# PSU.net
KiCad netlist of a schematic drawn in Altium Designer
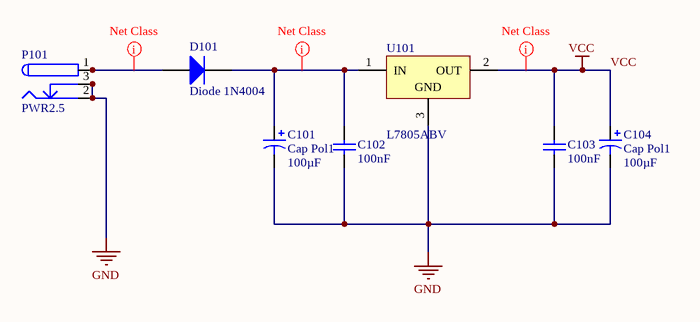
[diagram p0: PSU.SchDoc]

(export (version "E")
  (design (tool "Eeschema 10.0.6"))
  (components
    (comp (ref "C101")
      (value "Cap Pol1")
      (footprint "Tantalum_D")
      (description "Polarized Capacitor (Radial)")
      (fields (field (name "ALTIUM_VALUE") "100µF") (field (name "PUBLISHER") "Altium Limited"))
      (libsource (lib "Miscellaneous Devices") (part "Cap Pol1"))
    )
    (comp (ref "C102")
      (value "100nF")
      (footprint "RCL 0805")
      (description "Capacitor (Semiconductor SIM Model)")
      (fields (field (name "Comment") "Cap Semi") (field (name "PUBLISHER") "Altium Limited"))
      (libsource (lib "Miscellaneous Devices") (part "Cap Semi"))
    )
    (comp (ref "C103")
      (value "100nF")
      (footprint "RCL 0805")
      (description "Capacitor (Semiconductor SIM Model)")
      (fields (field (name "Comment") "Cap Semi") (field (name "PUBLISHER") "Altium Limited"))
      (libsource (lib "Miscellaneous Devices") (part "Cap Semi"))
    )
    (comp (ref "C104")
      (value "Cap Pol1")
      (footprint "Tantalum_D")
      (description "Polarized Capacitor (Radial)")
      (fields (field (name "ALTIUM_VALUE") "100µF") (field (name "PUBLISHER") "Altium Limited"))
      (libsource (lib "Miscellaneous Devices") (part "Cap Pol1"))
    )
    (comp (ref "D101")
      (value "Diode 1N4004")
      (footprint "DIO10.46-5.3x2.8")
      (description "1 Amp General Purpose Rectifier")
      (fields (field (name "PUBLISHER") "Altium Limited"))
      (libsource (lib "Miscellaneous Devices") (part "Diode 1N4004"))
    )
    (comp (ref "P101")
      (value "PWR2.5")
      (footprint "Power Jack 6mm")
      (description "Low Voltage Power Supply Connector")
      (fields (field (name "PUBLISHER") "Altium Limited"))
      (libsource (lib "Miscellaneous Connectors") (part "PWR2.5"))
    )
    (comp (ref "U101")
      (value "L7805ABV")
      (footprint "SFM-F3")
      (description "Precision 1A Regulator")
      (fields (field (name "PUBLISHER") "Altium Limited"))
      (libsource (lib "ST Power Mgt Voltage Regulator") (part "L7805ABV"))
    )
  )
  (nets
    (net (code "1") (name "GND") (class "Default")
      (node (ref "C101") (pin "2") (pinfunction "2_2") (pintype "passive"))
      (node (ref "C102") (pin "1") (pinfunction "1_1") (pintype "passive"))
      (node (ref "C103") (pin "1") (pinfunction "1_1") (pintype "passive"))
      (node (ref "C104") (pin "2") (pinfunction "2_2") (pintype "passive"))
      (node (ref "P101") (pin "2") (pinfunction "2_2") (pintype "power_in"))
      (node (ref "P101") (pin "2A") (pinfunction "2A_2A") (pintype "power_in"))
      (node (ref "P101") (pin "2B") (pinfunction "2B_2B") (pintype "power_in"))
      (node (ref "P101") (pin "3") (pinfunction "3_3") (pintype "power_in"))
      (node (ref "P101") (pin "3A") (pinfunction "3A_3A") (pintype "power_in"))
      (node (ref "P101") (pin "3B") (pinfunction "3B_3B") (pintype "power_in"))
      (node (ref "U101") (pin "3") (pinfunction "GND_3") (pintype "power_in"))
    )
    (net (code "2") (name "Net-(D101-A)") (class "Default")
      (node (ref "D101") (pin "1") (pinfunction "A_1") (pintype "passive"))
      (node (ref "P101") (pin "1") (pinfunction "1_1") (pintype "power_in"))
      (node (ref "P101") (pin "1A") (pinfunction "1A_1A") (pintype "power_in"))
      (node (ref "P101") (pin "1B") (pinfunction "1B_1B") (pintype "power_in"))
    )
    (net (code "3") (name "Net-(D101-K)") (class "Default")
      (node (ref "C101") (pin "1") (pinfunction "1_1") (pintype "passive"))
      (node (ref "C102") (pin "2") (pinfunction "2_2") (pintype "passive"))
      (node (ref "D101") (pin "2") (pinfunction "K_2") (pintype "passive"))
      (node (ref "U101") (pin "1") (pinfunction "IN_1") (pintype "power_in"))
    )
    (net (code "4") (name "VCC") (class "Default")
      (node (ref "C103") (pin "2") (pinfunction "2_2") (pintype "passive"))
      (node (ref "C104") (pin "1") (pinfunction "1_1") (pintype "passive"))
      (node (ref "U101") (pin "2") (pinfunction "OUT_2") (pintype "power_in"))
    )
  )
)
